# microSDAdaptor.net
KiCad netlist of a schematic drawn in Altium Designer
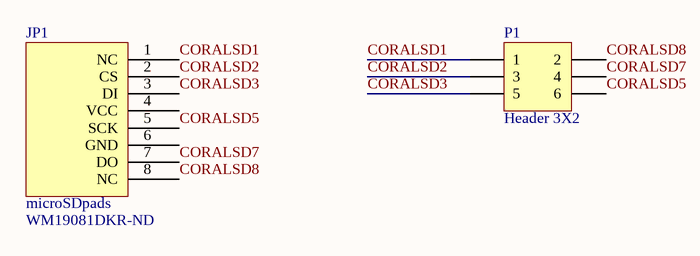
[diagram p0: microSDAdaptor.SchDoc]

(export (version "E")
  (design (tool "Eeschema 10.0.6"))
  (components
    (comp (ref "JP1")
      (value "microSDpads")
      (footprint "microSDtabs")
      (fields (field (name "SUPPLIER PART NUMBER 1") "WM19081DKR-ND"))
      (libsource (lib "Loggerhead") (part "microSDpads"))
    )
    (comp (ref "P1")
      (value "Header 3X2")
      (footprint "HDR2X3")
      (description "Header, 3-Pin, Dual row")
      (fields (field (name "PUBLISHER") "Altium Limited"))
      (libsource (lib "Miscellaneous Connectors") (part "Header 3X2"))
    )
  )
  (nets
    (net (code "1") (name "/CORALSD1") (class "Default")
      (node (ref "JP1") (pin "1") (pinfunction "NC_1") (pintype "passive"))
      (node (ref "P1") (pin "1") (pinfunction "1_1") (pintype "passive"))
    )
    (net (code "2") (name "/CORALSD2") (class "Default")
      (node (ref "JP1") (pin "2") (pinfunction "CS_2") (pintype "passive"))
      (node (ref "P1") (pin "3") (pinfunction "3_3") (pintype "passive"))
    )
    (net (code "3") (name "/CORALSD3") (class "Default")
      (node (ref "JP1") (pin "3") (pinfunction "DI_3") (pintype "passive"))
      (node (ref "P1") (pin "5") (pinfunction "5_5") (pintype "passive"))
    )
    (net (code "4") (name "/CORALSD5") (class "Default")
      (node (ref "JP1") (pin "5") (pinfunction "SCK_5") (pintype "passive"))
      (node (ref "P1") (pin "6") (pinfunction "6_6") (pintype "passive"))
    )
    (net (code "5") (name "/CORALSD7") (class "Default")
      (node (ref "JP1") (pin "7") (pinfunction "DO_7") (pintype "passive"))
      (node (ref "P1") (pin "4") (pinfunction "4_4") (pintype "passive"))
    )
    (net (code "6") (name "/CORALSD8") (class "Default")
      (node (ref "JP1") (pin "8") (pinfunction "NC_8") (pintype "passive"))
      (node (ref "P1") (pin "2") (pinfunction "2_2") (pintype "passive"))
    )
    (net (code "7") (name "unconnected-(JP1-GND-Pad6)") (class "Default")
      (node (ref "JP1") (pin "6") (pinfunction "GND_6") (pintype "passive"))
    )
    (net (code "8") (name "unconnected-(JP1-VCC-Pad4)") (class "Default")
      (node (ref "JP1") (pin "4") (pinfunction "VCC_4") (pintype "passive"))
    )
  )
)
